# Board.net
KiCad netlist of a schematic drawn in Altium Designer
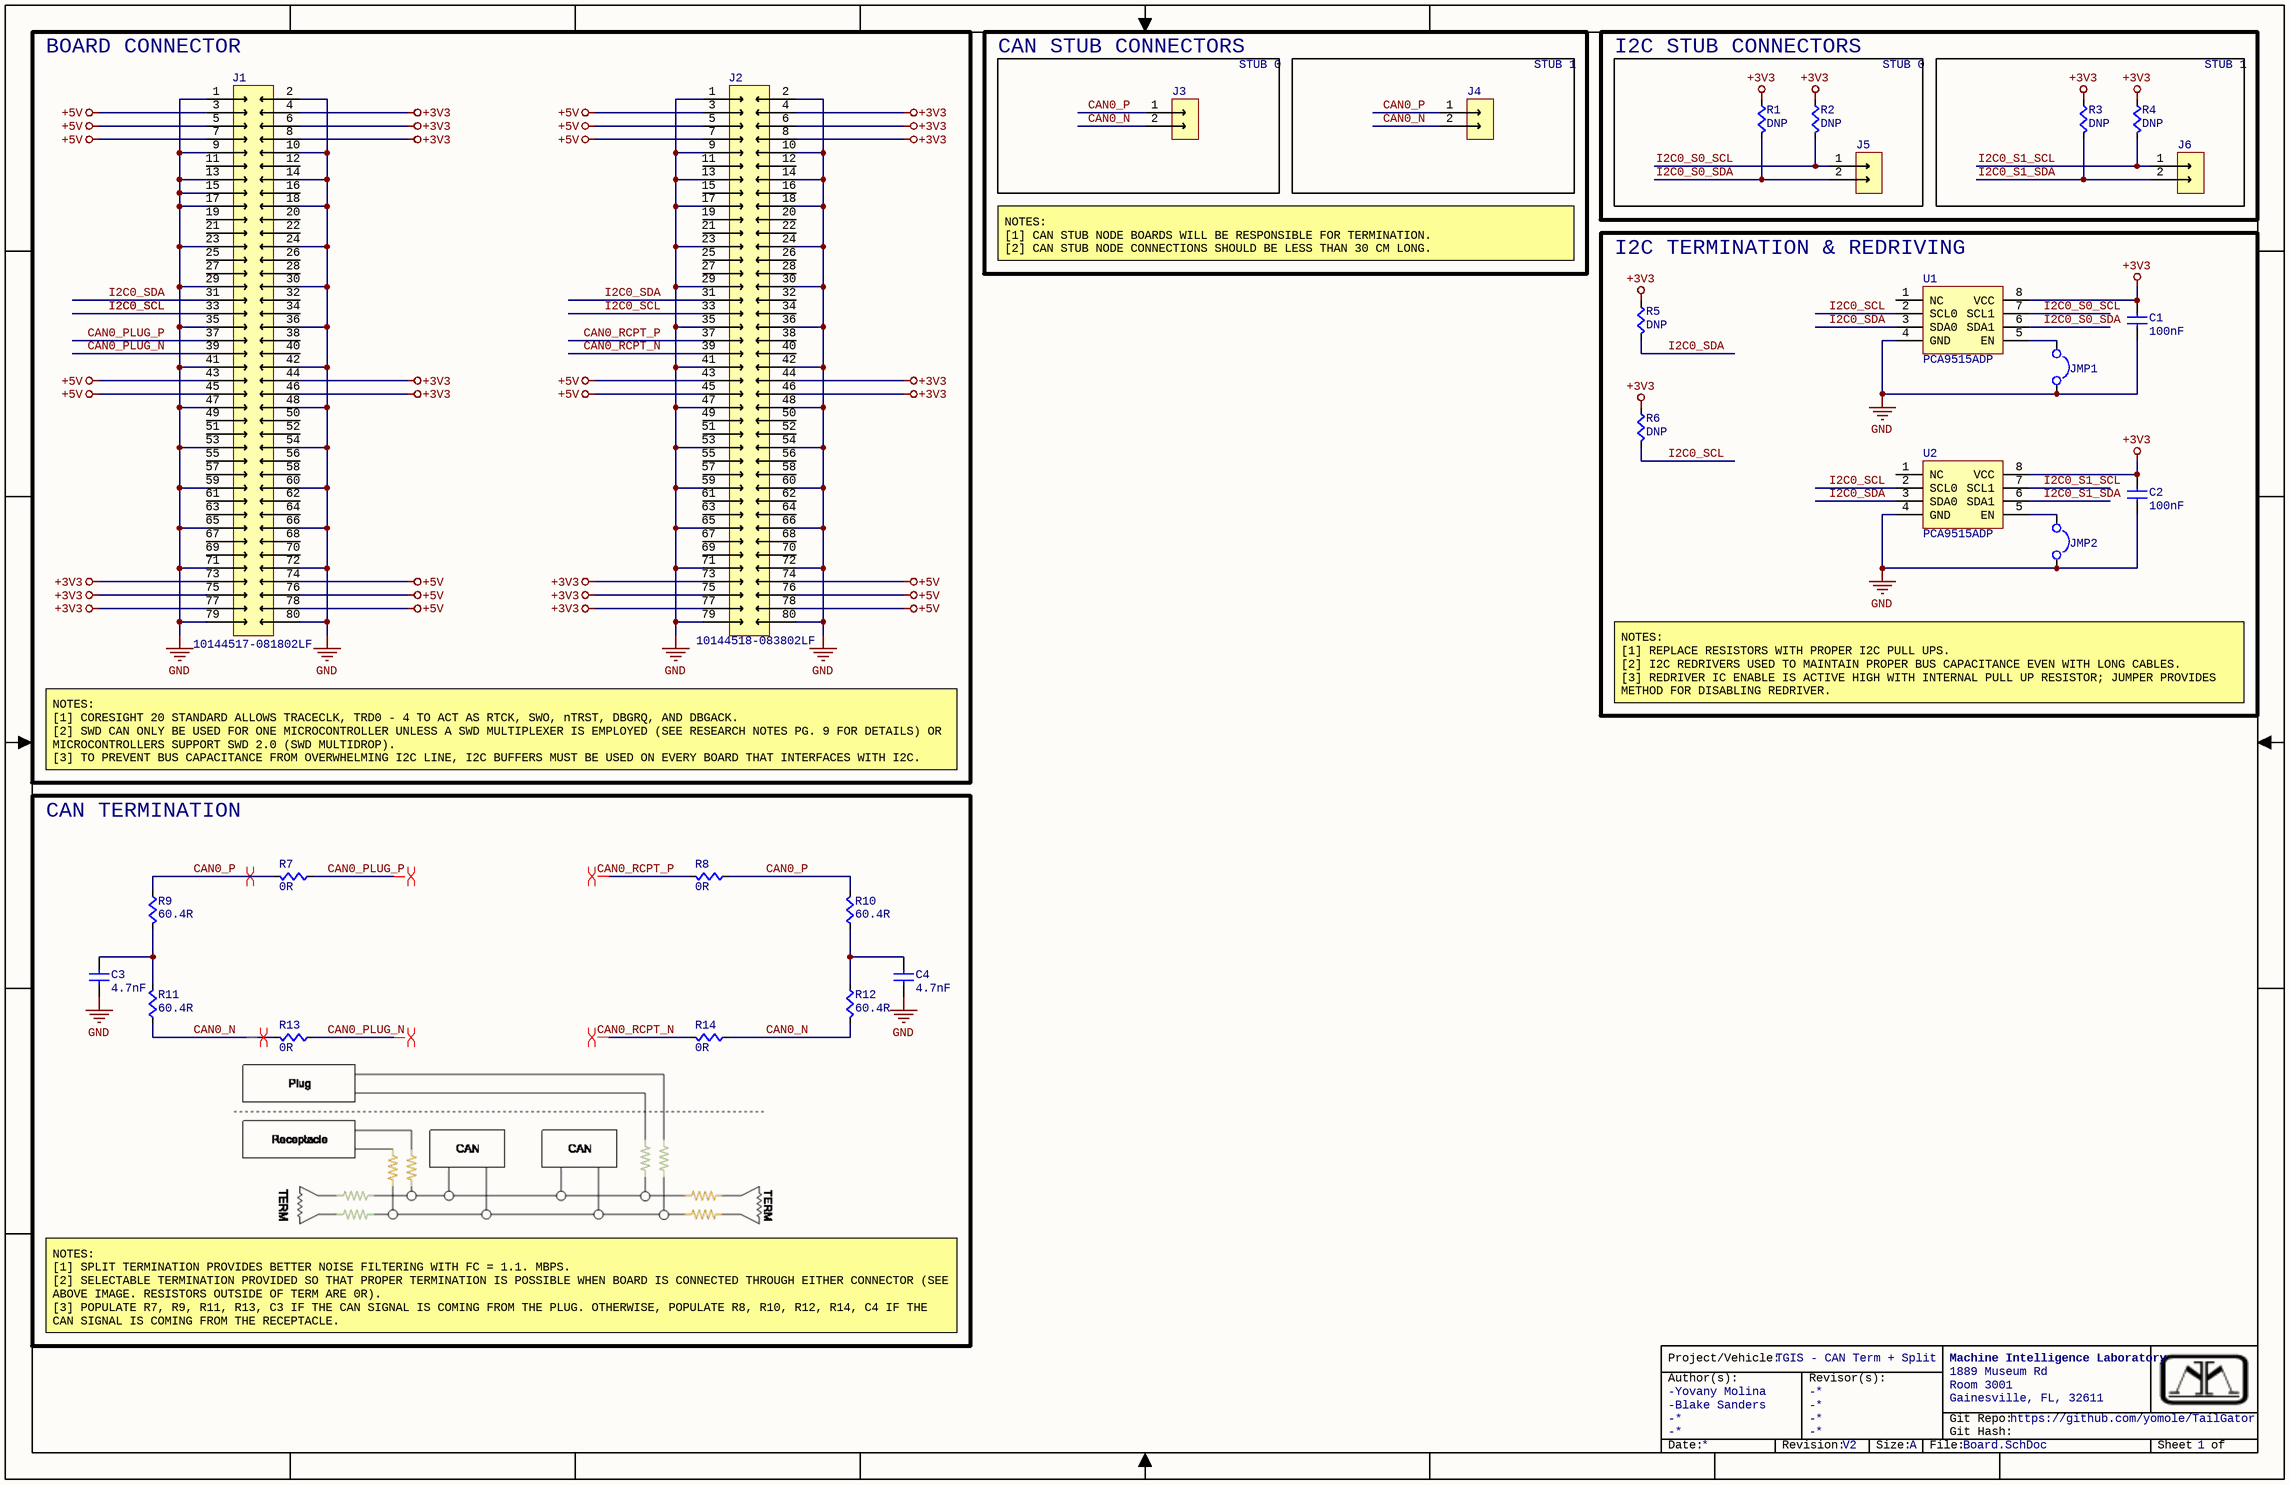
[diagram p0: Board.SchDoc]

(export (version "E")
  (design (tool "Eeschema 10.0.6"))
  (components
    (comp (ref "C1")
      (value "100nF")
      (footprint "CAPC0603")
      (description "Ceramic Capacitor, Multilayer, Cera")
      (fields (field (name "PART NUMBER") "CC0603KRX7R7BB104") (field (name "MANUFACTURER") "Yageo"))
      (libsource (lib "Parts") (part "NP_Capacitor"))
    )
    (comp (ref "C2")
      (value "100nF")
      (footprint "CAPC0603")
      (description "Ceramic Capacitor, Multilayer, Cera")
      (fields (field (name "PART NUMBER") "CC0603KRX7R7BB104") (field (name "MANUFACTURER") "Yageo"))
      (libsource (lib "Parts") (part "NP_Capacitor"))
    )
    (comp (ref "C3")
      (value "4.7nF")
      (footprint "CAPC0603")
      (description "Ceramic Capacitor, Multilayer, Cera")
      (fields (field (name "PART NUMBER") "CC0603JPX7R9BB472") (field (name "MANUFACTURER") "Yageo"))
      (libsource (lib "Parts") (part "NP_Capacitor"))
    )
    (comp (ref "C4")
      (value "4.7nF")
      (footprint "CAPC0603")
      (description "Ceramic Capacitor, Multilayer, Cera")
      (fields (field (name "PART NUMBER") "CC0603JPX7R9BB472") (field (name "MANUFACTURER") "Yageo"))
      (libsource (lib "Parts") (part "NP_Capacitor"))
    )
    (comp (ref "J1")
      (value "10144517-081802LF")
      (footprint "AMPHENOL_10144517-081802LF")
      (description "CONN RCPT 1 80POS SMD GOLD")
      (libsource (lib "TGIS") (part "10144517-081802LF"))
    )
    (comp (ref "J2")
      (value "10144518-083802LF")
      (footprint "AMPHENOL_10144518-083802LF")
      (description "CONN PLUG 3 80POS SMD GOLD")
      (libsource (lib "TGIS") (part "10144518-083802LF"))
    )
    (comp (ref "J3")
      (value "0353630260")
      (footprint "MOLEX-HDR-1X2-SHERLOCK-HORZ")
      (fields (field (name "MANUFACTURER") "Molex Inc"))
      (libsource (lib "Connectors") (part "SHERLOCK-1x2-RA"))
    )
    (comp (ref "J4")
      (value "0353630260")
      (footprint "MOLEX-HDR-1X2-SHERLOCK-HORZ")
      (fields (field (name "MANUFACTURER") "Molex Inc"))
      (libsource (lib "Connectors") (part "SHERLOCK-1x2-RA"))
    )
    (comp (ref "J5")
      (value "0353630260")
      (footprint "MOLEX-HDR-1X2-SHERLOCK-HORZ")
      (fields (field (name "MANUFACTURER") "Molex Inc"))
      (libsource (lib "Connectors") (part "SHERLOCK-1x2-RA"))
    )
    (comp (ref "J6")
      (value "0353630260")
      (footprint "MOLEX-HDR-1X2-SHERLOCK-HORZ")
      (fields (field (name "MANUFACTURER") "Molex Inc"))
      (libsource (lib "Connectors") (part "SHERLOCK-1x2-RA"))
    )
    (comp (ref "JMP1")
      (value "2 Pin Header")
      (footprint "2PinJumper")
      (description "2 Position Jumper")
      (libsource (lib "Misc") (part "Jumper_2Pin"))
    )
    (comp (ref "JMP2")
      (value "2 Pin Header")
      (footprint "2PinJumper")
      (description "2 Position Jumper")
      (libsource (lib "Misc") (part "Jumper_2Pin"))
    )
    (comp (ref "R1")
      (value "DNP")
      (footprint "RES0603")
      (description "(DO NOT PLACE) Resistor")
      (libsource (lib "DNP") (part "Resistor_DNP"))
    )
    (comp (ref "R2")
      (value "DNP")
      (footprint "RES0603")
      (description "(DO NOT PLACE) Resistor")
      (libsource (lib "DNP") (part "Resistor_DNP"))
    )
    (comp (ref "R3")
      (value "DNP")
      (footprint "RES0603")
      (description "(DO NOT PLACE) Resistor")
      (libsource (lib "DNP") (part "Resistor_DNP"))
    )
    (comp (ref "R4")
      (value "DNP")
      (footprint "RES0603")
      (description "(DO NOT PLACE) Resistor")
      (libsource (lib "DNP") (part "Resistor_DNP"))
    )
    (comp (ref "R5")
      (value "DNP")
      (footprint "RES0603")
      (description "(DO NOT PLACE) Resistor")
      (libsource (lib "DNP") (part "Resistor_DNP"))
    )
    (comp (ref "R6")
      (value "DNP")
      (footprint "RES0603")
      (description "(DO NOT PLACE) Resistor")
      (libsource (lib "DNP") (part "Resistor_DNP"))
    )
    (comp (ref "R7")
      (value "0R")
      (footprint "RES0603")
      (description "Fixed Resistor, Metal Glaze/thick F")
      (fields (field (name "PART NUMBER") "RC0603FR-070RL") (field (name "POWER") "100mW"))
      (libsource (lib "Parts") (part "Resistor"))
    )
    (comp (ref "R8")
      (value "0R")
      (footprint "RES0603")
      (description "Fixed Resistor, Metal Glaze/thick F")
      (fields (field (name "PART NUMBER") "RC0603FR-070RL") (field (name "POWER") "100mW"))
      (libsource (lib "Parts") (part "Resistor"))
    )
    (comp (ref "R9")
      (value "60.4R")
      (footprint "RES0603")
      (description "Fixed Resistor, Metal Glaze/thick F")
      (fields (field (name "PART NUMBER") "RC0603FR-0760R4L") (field (name "POWER") "100mW"))
      (libsource (lib "Parts") (part "Resistor"))
    )
    (comp (ref "R10")
      (value "60.4R")
      (footprint "RES0603")
      (description "Fixed Resistor, Metal Glaze/thick F")
      (fields (field (name "PART NUMBER") "RC0603FR-0760R4L") (field (name "POWER") "100mW"))
      (libsource (lib "Parts") (part "Resistor"))
    )
    (comp (ref "R11")
      (value "60.4R")
      (footprint "RES0603")
      (description "Fixed Resistor, Metal Glaze/thick F")
      (fields (field (name "PART NUMBER") "RC0603FR-0760R4L") (field (name "POWER") "100mW"))
      (libsource (lib "Parts") (part "Resistor"))
    )
    (comp (ref "R12")
      (value "60.4R")
      (footprint "RES0603")
      (description "Fixed Resistor, Metal Glaze/thick F")
      (fields (field (name "PART NUMBER") "RC0603FR-0760R4L") (field (name "POWER") "100mW"))
      (libsource (lib "Parts") (part "Resistor"))
    )
    (comp (ref "R13")
      (value "0R")
      (footprint "RES0603")
      (description "Fixed Resistor, Metal Glaze/thick F")
      (fields (field (name "PART NUMBER") "RC0603FR-070RL") (field (name "POWER") "100mW"))
      (libsource (lib "Parts") (part "Resistor"))
    )
    (comp (ref "R14")
      (value "0R")
      (footprint "RES0603")
      (description "Fixed Resistor, Metal Glaze/thick F")
      (fields (field (name "PART NUMBER") "RC0603FR-070RL") (field (name "POWER") "100mW"))
      (libsource (lib "Parts") (part "Resistor"))
    )
    (comp (ref "U1")
      (value "PCA9515ADP")
      (footprint "SOP65P490X110-8N")
      (description "IC REDRIVER I2C 2CH 8TSSOP")
      (libsource (lib "TGIS") (part "PCA9515ADP"))
    )
    (comp (ref "U2")
      (value "PCA9515ADP")
      (footprint "SOP65P490X110-8N")
      (description "IC REDRIVER I2C 2CH 8TSSOP")
      (libsource (lib "TGIS") (part "PCA9515ADP"))
    )
  )
  (nets
    (net (code "1") (name "+3V3") (class "Default")
      (node (ref "C1") (pin "2") (pinfunction "B_2") (pintype "passive"))
      (node (ref "C2") (pin "2") (pinfunction "B_2") (pintype "passive"))
      (node (ref "J1") (pin "4") (pinfunction "4_4") (pintype "passive"))
      (node (ref "J1") (pin "44") (pinfunction "44_44") (pintype "passive"))
      (node (ref "J1") (pin "46") (pinfunction "46_46") (pintype "passive"))
      (node (ref "J1") (pin "6") (pinfunction "6_6") (pintype "passive"))
      (node (ref "J1") (pin "73") (pinfunction "73_73") (pintype "passive"))
      (node (ref "J1") (pin "75") (pinfunction "75_75") (pintype "passive"))
      (node (ref "J1") (pin "77") (pinfunction "77_77") (pintype "passive"))
      (node (ref "J1") (pin "8") (pinfunction "8_8") (pintype "passive"))
      (node (ref "J2") (pin "4") (pinfunction "4_4") (pintype "passive"))
      (node (ref "J2") (pin "44") (pinfunction "44_44") (pintype "passive"))
      (node (ref "J2") (pin "46") (pinfunction "46_46") (pintype "passive"))
      (node (ref "J2") (pin "6") (pinfunction "6_6") (pintype "passive"))
      (node (ref "J2") (pin "73") (pinfunction "73_73") (pintype "passive"))
      (node (ref "J2") (pin "75") (pinfunction "75_75") (pintype "passive"))
      (node (ref "J2") (pin "77") (pinfunction "77_77") (pintype "passive"))
      (node (ref "J2") (pin "8") (pinfunction "8_8") (pintype "passive"))
      (node (ref "R1") (pin "2") (pinfunction "B_2") (pintype "passive"))
      (node (ref "R2") (pin "2") (pinfunction "B_2") (pintype "passive"))
      (node (ref "R3") (pin "2") (pinfunction "B_2") (pintype "passive"))
      (node (ref "R4") (pin "2") (pinfunction "B_2") (pintype "passive"))
      (node (ref "R5") (pin "2") (pinfunction "B_2") (pintype "passive"))
      (node (ref "R6") (pin "2") (pinfunction "B_2") (pintype "passive"))
      (node (ref "U1") (pin "8") (pinfunction "VCC_8") (pintype "passive"))
      (node (ref "U2") (pin "8") (pinfunction "VCC_8") (pintype "passive"))
    )
    (net (code "2") (name "+5V") (class "Default")
      (node (ref "J1") (pin "3") (pinfunction "3_3") (pintype "passive"))
      (node (ref "J1") (pin "43") (pinfunction "43_43") (pintype "passive"))
      (node (ref "J1") (pin "45") (pinfunction "45_45") (pintype "passive"))
      (node (ref "J1") (pin "5") (pinfunction "5_5") (pintype "passive"))
      (node (ref "J1") (pin "7") (pinfunction "7_7") (pintype "passive"))
      (node (ref "J1") (pin "74") (pinfunction "74_74") (pintype "passive"))
      (node (ref "J1") (pin "76") (pinfunction "76_76") (pintype "passive"))
      (node (ref "J1") (pin "78") (pinfunction "78_78") (pintype "passive"))
      (node (ref "J2") (pin "3") (pinfunction "3_3") (pintype "passive"))
      (node (ref "J2") (pin "43") (pinfunction "43_43") (pintype "passive"))
      (node (ref "J2") (pin "45") (pinfunction "45_45") (pintype "passive"))
      (node (ref "J2") (pin "5") (pinfunction "5_5") (pintype "passive"))
      (node (ref "J2") (pin "7") (pinfunction "7_7") (pintype "passive"))
      (node (ref "J2") (pin "74") (pinfunction "74_74") (pintype "passive"))
      (node (ref "J2") (pin "76") (pinfunction "76_76") (pintype "passive"))
      (node (ref "J2") (pin "78") (pinfunction "78_78") (pintype "passive"))
    )
    (net (code "3") (name "/CAN0_N") (class "Default")
      (node (ref "J3") (pin "2") (pinfunction "2_2") (pintype "passive"))
      (node (ref "J4") (pin "2") (pinfunction "2_2") (pintype "passive"))
      (node (ref "R11") (pin "2") (pinfunction "B_2") (pintype "passive"))
      (node (ref "R12") (pin "2") (pinfunction "B_2") (pintype "passive"))
      (node (ref "R13") (pin "1") (pinfunction "A_1") (pintype "passive"))
      (node (ref "R14") (pin "2") (pinfunction "B_2") (pintype "passive"))
    )
    (net (code "4") (name "/CAN0_P") (class "Default")
      (node (ref "J3") (pin "1") (pinfunction "1_1") (pintype "passive"))
      (node (ref "J4") (pin "1") (pinfunction "1_1") (pintype "passive"))
      (node (ref "R10") (pin "2") (pinfunction "B_2") (pintype "passive"))
      (node (ref "R7") (pin "1") (pinfunction "A_1") (pintype "passive"))
      (node (ref "R8") (pin "2") (pinfunction "B_2") (pintype "passive"))
      (node (ref "R9") (pin "2") (pinfunction "B_2") (pintype "passive"))
    )
    (net (code "5") (name "/CAN0_PLUG_N") (class "Default")
      (node (ref "J1") (pin "39") (pinfunction "39_39") (pintype "passive"))
      (node (ref "R13") (pin "2") (pinfunction "B_2") (pintype "passive"))
    )
    (net (code "6") (name "/CAN0_PLUG_P") (class "Default")
      (node (ref "J1") (pin "37") (pinfunction "37_37") (pintype "passive"))
      (node (ref "R7") (pin "2") (pinfunction "B_2") (pintype "passive"))
    )
    (net (code "7") (name "/CAN0_RCPT_N") (class "Default")
      (node (ref "J2") (pin "39") (pinfunction "39_39") (pintype "passive"))
      (node (ref "R14") (pin "1") (pinfunction "A_1") (pintype "passive"))
    )
    (net (code "8") (name "/CAN0_RCPT_P") (class "Default")
      (node (ref "J2") (pin "37") (pinfunction "37_37") (pintype "passive"))
      (node (ref "R8") (pin "1") (pinfunction "A_1") (pintype "passive"))
    )
    (net (code "9") (name "/I2C0_S0_SCL") (class "Default")
      (node (ref "J5") (pin "1") (pinfunction "1_1") (pintype "passive"))
      (node (ref "R2") (pin "1") (pinfunction "A_1") (pintype "passive"))
      (node (ref "U1") (pin "7") (pinfunction "SCL1_7") (pintype "passive"))
    )
    (net (code "10") (name "/I2C0_S0_SDA") (class "Default")
      (node (ref "J5") (pin "2") (pinfunction "2_2") (pintype "passive"))
      (node (ref "R1") (pin "1") (pinfunction "A_1") (pintype "passive"))
      (node (ref "U1") (pin "6") (pinfunction "SDA1_6") (pintype "passive"))
    )
    (net (code "11") (name "/I2C0_S1_SCL") (class "Default")
      (node (ref "J6") (pin "1") (pinfunction "1_1") (pintype "passive"))
      (node (ref "R4") (pin "1") (pinfunction "A_1") (pintype "passive"))
      (node (ref "U2") (pin "7") (pinfunction "SCL1_7") (pintype "passive"))
    )
    (net (code "12") (name "/I2C0_S1_SDA") (class "Default")
      (node (ref "J6") (pin "2") (pinfunction "2_2") (pintype "passive"))
      (node (ref "R3") (pin "1") (pinfunction "A_1") (pintype "passive"))
      (node (ref "U2") (pin "6") (pinfunction "SDA1_6") (pintype "passive"))
    )
    (net (code "13") (name "/I2C0_SCL") (class "Default")
      (node (ref "J1") (pin "33") (pinfunction "33_33") (pintype "passive"))
      (node (ref "J2") (pin "33") (pinfunction "33_33") (pintype "passive"))
      (node (ref "R6") (pin "1") (pinfunction "A_1") (pintype "passive"))
      (node (ref "U1") (pin "2") (pinfunction "SCL0_2") (pintype "passive"))
      (node (ref "U2") (pin "2") (pinfunction "SCL0_2") (pintype "passive"))
    )
    (net (code "14") (name "/I2C0_SDA") (class "Default")
      (node (ref "J1") (pin "31") (pinfunction "31_31") (pintype "passive"))
      (node (ref "J2") (pin "31") (pinfunction "31_31") (pintype "passive"))
      (node (ref "R5") (pin "1") (pinfunction "A_1") (pintype "passive"))
      (node (ref "U1") (pin "3") (pinfunction "SDA0_3") (pintype "passive"))
      (node (ref "U2") (pin "3") (pinfunction "SDA0_3") (pintype "passive"))
    )
    (net (code "15") (name "GND") (class "Default")
      (node (ref "C1") (pin "1") (pinfunction "A_1") (pintype "passive"))
      (node (ref "C2") (pin "1") (pinfunction "A_1") (pintype "passive"))
      (node (ref "C3") (pin "2") (pinfunction "B_2") (pintype "passive"))
      (node (ref "C4") (pin "2") (pinfunction "B_2") (pintype "passive"))
      (node (ref "J1") (pin "1") (pinfunction "1_1") (pintype "passive"))
      (node (ref "J1") (pin "10") (pinfunction "10_10") (pintype "passive"))
      (node (ref "J1") (pin "13") (pinfunction "13_13") (pintype "passive"))
      (node (ref "J1") (pin "14") (pinfunction "14_14") (pintype "passive"))
      (node (ref "J1") (pin "15") (pinfunction "15_15") (pintype "passive"))
      (node (ref "J1") (pin "17") (pinfunction "17_17") (pintype "passive"))
      (node (ref "J1") (pin "18") (pinfunction "18_18") (pintype "passive"))
      (node (ref "J1") (pin "2") (pinfunction "2_2") (pintype "passive"))
      (node (ref "J1") (pin "23") (pinfunction "23_23") (pintype "passive"))
      (node (ref "J1") (pin "24") (pinfunction "24_24") (pintype "passive"))
      (node (ref "J1") (pin "29") (pinfunction "29_29") (pintype "passive"))
      (node (ref "J1") (pin "30") (pinfunction "30_30") (pintype "passive"))
      (node (ref "J1") (pin "35") (pinfunction "35_35") (pintype "passive"))
      (node (ref "J1") (pin "36") (pinfunction "36_36") (pintype "passive"))
      (node (ref "J1") (pin "41") (pinfunction "41_41") (pintype "passive"))
      (node (ref "J1") (pin "42") (pinfunction "42_42") (pintype "passive"))
      (node (ref "J1") (pin "47") (pinfunction "47_47") (pintype "passive"))
      (node (ref "J1") (pin "48") (pinfunction "48_48") (pintype "passive"))
      (node (ref "J1") (pin "53") (pinfunction "53_53") (pintype "passive"))
      (node (ref "J1") (pin "54") (pinfunction "54_54") (pintype "passive"))
      (node (ref "J1") (pin "59") (pinfunction "59_59") (pintype "passive"))
      (node (ref "J1") (pin "60") (pinfunction "60_60") (pintype "passive"))
      (node (ref "J1") (pin "65") (pinfunction "65_65") (pintype "passive"))
      (node (ref "J1") (pin "66") (pinfunction "66_66") (pintype "passive"))
      (node (ref "J1") (pin "71") (pinfunction "71_71") (pintype "passive"))
      (node (ref "J1") (pin "72") (pinfunction "72_72") (pintype "passive"))
      (node (ref "J1") (pin "79") (pinfunction "79_79") (pintype "passive"))
      (node (ref "J1") (pin "80") (pinfunction "80_80") (pintype "passive"))
      (node (ref "J1") (pin "9") (pinfunction "9_9") (pintype "passive"))
      (node (ref "J2") (pin "1") (pinfunction "1_1") (pintype "passive"))
      (node (ref "J2") (pin "10") (pinfunction "10_10") (pintype "passive"))
      (node (ref "J2") (pin "13") (pinfunction "13_13") (pintype "passive"))
      (node (ref "J2") (pin "14") (pinfunction "14_14") (pintype "passive"))
      (node (ref "J2") (pin "17") (pinfunction "17_17") (pintype "passive"))
      (node (ref "J2") (pin "18") (pinfunction "18_18") (pintype "passive"))
      (node (ref "J2") (pin "2") (pinfunction "2_2") (pintype "passive"))
      (node (ref "J2") (pin "23") (pinfunction "23_23") (pintype "passive"))
      (node (ref "J2") (pin "24") (pinfunction "24_24") (pintype "passive"))
      (node (ref "J2") (pin "29") (pinfunction "29_29") (pintype "passive"))
      (node (ref "J2") (pin "30") (pinfunction "30_30") (pintype "passive"))
      (node (ref "J2") (pin "35") (pinfunction "35_35") (pintype "passive"))
      (node (ref "J2") (pin "36") (pinfunction "36_36") (pintype "passive"))
      (node (ref "J2") (pin "41") (pinfunction "41_41") (pintype "passive"))
      (node (ref "J2") (pin "42") (pinfunction "42_42") (pintype "passive"))
      (node (ref "J2") (pin "47") (pinfunction "47_47") (pintype "passive"))
      (node (ref "J2") (pin "48") (pinfunction "48_48") (pintype "passive"))
      (node (ref "J2") (pin "53") (pinfunction "53_53") (pintype "passive"))
      (node (ref "J2") (pin "54") (pinfunction "54_54") (pintype "passive"))
      (node (ref "J2") (pin "59") (pinfunction "59_59") (pintype "passive"))
      (node (ref "J2") (pin "60") (pinfunction "60_60") (pintype "passive"))
      (node (ref "J2") (pin "65") (pinfunction "65_65") (pintype "passive"))
      (node (ref "J2") (pin "66") (pinfunction "66_66") (pintype "passive"))
      (node (ref "J2") (pin "71") (pinfunction "71_71") (pintype "passive"))
      (node (ref "J2") (pin "72") (pinfunction "72_72") (pintype "passive"))
      (node (ref "J2") (pin "79") (pinfunction "79_79") (pintype "passive"))
      (node (ref "J2") (pin "80") (pinfunction "80_80") (pintype "passive"))
      (node (ref "J2") (pin "9") (pinfunction "9_9") (pintype "passive"))
      (node (ref "JMP1") (pin "2") (pinfunction "2_2") (pintype "passive"))
      (node (ref "JMP2") (pin "2") (pinfunction "2_2") (pintype "passive"))
      (node (ref "U1") (pin "4") (pinfunction "GND_4") (pintype "passive"))
      (node (ref "U2") (pin "4") (pinfunction "GND_4") (pintype "passive"))
    )
    (net (code "16") (name "Net-(C3-A)") (class "Default")
      (node (ref "C3") (pin "1") (pinfunction "A_1") (pintype "passive"))
      (node (ref "R11") (pin "1") (pinfunction "A_1") (pintype "passive"))
      (node (ref "R9") (pin "1") (pinfunction "A_1") (pintype "passive"))
    )
    (net (code "17") (name "Net-(C4-A)") (class "Default")
      (node (ref "C4") (pin "1") (pinfunction "A_1") (pintype "passive"))
      (node (ref "R10") (pin "1") (pinfunction "A_1") (pintype "passive"))
      (node (ref "R12") (pin "1") (pinfunction "A_1") (pintype "passive"))
    )
    (net (code "18") (name "Net-(U1-EN)") (class "Default")
      (node (ref "JMP1") (pin "1") (pinfunction "1_1") (pintype "passive"))
      (node (ref "U1") (pin "5") (pinfunction "EN_5") (pintype "passive"))
    )
    (net (code "19") (name "Net-(U2-EN)") (class "Default")
      (node (ref "JMP2") (pin "1") (pinfunction "1_1") (pintype "passive"))
      (node (ref "U2") (pin "5") (pinfunction "EN_5") (pintype "passive"))
    )
    (net (code "20") (name "unconnected-(J1-Pad11)") (class "Default")
      (node (ref "J1") (pin "11") (pinfunction "11_11") (pintype "passive"))
    )
    (net (code "21") (name "unconnected-(J1-Pad12)") (class "Default")
      (node (ref "J1") (pin "12") (pinfunction "12_12") (pintype "passive"))
    )
    (net (code "22") (name "unconnected-(J1-Pad16)") (class "Default")
      (node (ref "J1") (pin "16") (pinfunction "16_16") (pintype "passive"))
    )
    (net (code "23") (name "unconnected-(J1-Pad19)") (class "Default")
      (node (ref "J1") (pin "19") (pinfunction "19_19") (pintype "passive"))
    )
    (net (code "24") (name "unconnected-(J1-Pad20)") (class "Default")
      (node (ref "J1") (pin "20") (pinfunction "20_20") (pintype "passive"))
    )
    (net (code "25") (name "unconnected-(J1-Pad21)") (class "Default")
      (node (ref "J1") (pin "21") (pinfunction "21_21") (pintype "passive"))
    )
    (net (code "26") (name "unconnected-(J1-Pad22)") (class "Default")
      (node (ref "J1") (pin "22") (pinfunction "22_22") (pintype "passive"))
    )
    (net (code "27") (name "unconnected-(J1-Pad25)") (class "Default")
      (node (ref "J1") (pin "25") (pinfunction "25_25") (pintype "passive"))
    )
    (net (code "28") (name "unconnected-(J1-Pad26)") (class "Default")
      (node (ref "J1") (pin "26") (pinfunction "26_26") (pintype "passive"))
    )
    (net (code "29") (name "unconnected-(J1-Pad27)") (class "Default")
      (node (ref "J1") (pin "27") (pinfunction "27_27") (pintype "passive"))
    )
    (net (code "30") (name "unconnected-(J1-Pad28)") (class "Default")
      (node (ref "J1") (pin "28") (pinfunction "28_28") (pintype "passive"))
    )
    (net (code "31") (name "unconnected-(J1-Pad32)") (class "Default")
      (node (ref "J1") (pin "32") (pinfunction "32_32") (pintype "passive"))
    )
    (net (code "32") (name "unconnected-(J1-Pad34)") (class "Default")
      (node (ref "J1") (pin "34") (pinfunction "34_34") (pintype "passive"))
    )
    (net (code "33") (name "unconnected-(J1-Pad38)") (class "Default")
      (node (ref "J1") (pin "38") (pinfunction "38_38") (pintype "passive"))
    )
    (net (code "34") (name "unconnected-(J1-Pad40)") (class "Default")
      (node (ref "J1") (pin "40") (pinfunction "40_40") (pintype "passive"))
    )
    (net (code "35") (name "unconnected-(J1-Pad49)") (class "Default")
      (node (ref "J1") (pin "49") (pinfunction "49_49") (pintype "passive"))
    )
    (net (code "36") (name "unconnected-(J1-Pad50)") (class "Default")
      (node (ref "J1") (pin "50") (pinfunction "50_50") (pintype "passive"))
    )
    (net (code "37") (name "unconnected-(J1-Pad51)") (class "Default")
      (node (ref "J1") (pin "51") (pinfunction "51_51") (pintype "passive"))
    )
    (net (code "38") (name "unconnected-(J1-Pad52)") (class "Default")
      (node (ref "J1") (pin "52") (pinfunction "52_52") (pintype "passive"))
    )
    (net (code "39") (name "unconnected-(J1-Pad55)") (class "Default")
      (node (ref "J1") (pin "55") (pinfunction "55_55") (pintype "passive"))
    )
    (net (code "40") (name "unconnected-(J1-Pad56)") (class "Default")
      (node (ref "J1") (pin "56") (pinfunction "56_56") (pintype "passive"))
    )
    (net (code "41") (name "unconnected-(J1-Pad57)") (class "Default")
      (node (ref "J1") (pin "57") (pinfunction "57_57") (pintype "passive"))
    )
    (net (code "42") (name "unconnected-(J1-Pad58)") (class "Default")
      (node (ref "J1") (pin "58") (pinfunction "58_58") (pintype "passive"))
    )
    (net (code "43") (name "unconnected-(J1-Pad61)") (class "Default")
      (node (ref "J1") (pin "61") (pinfunction "61_61") (pintype "passive"))
    )
    (net (code "44") (name "unconnected-(J1-Pad62)") (class "Default")
      (node (ref "J1") (pin "62") (pinfunction "62_62") (pintype "passive"))
    )
    (net (code "45") (name "unconnected-(J1-Pad63)") (class "Default")
      (node (ref "J1") (pin "63") (pinfunction "63_63") (pintype "passive"))
    )
    (net (code "46") (name "unconnected-(J1-Pad64)") (class "Default")
      (node (ref "J1") (pin "64") (pinfunction "64_64") (pintype "passive"))
    )
    (net (code "47") (name "unconnected-(J1-Pad67)") (class "Default")
      (node (ref "J1") (pin "67") (pinfunction "67_67") (pintype "passive"))
    )
    (net (code "48") (name "unconnected-(J1-Pad68)") (class "Default")
      (node (ref "J1") (pin "68") (pinfunction "68_68") (pintype "passive"))
    )
    (net (code "49") (name "unconnected-(J1-Pad69)") (class "Default")
      (node (ref "J1") (pin "69") (pinfunction "69_69") (pintype "passive"))
    )
    (net (code "50") (name "unconnected-(J1-Pad70)") (class "Default")
      (node (ref "J1") (pin "70") (pinfunction "70_70") (pintype "passive"))
    )
    (net (code "51") (name "unconnected-(J2-Pad11)") (class "Default")
      (node (ref "J2") (pin "11") (pinfunction "11_11") (pintype "passive"))
    )
    (net (code "52") (name "unconnected-(J2-Pad12)") (class "Default")
      (node (ref "J2") (pin "12") (pinfunction "12_12") (pintype "passive"))
    )
    (net (code "53") (name "unconnected-(J2-Pad15)") (class "Default")
      (node (ref "J2") (pin "15") (pinfunction "15_15") (pintype "passive"))
    )
    (net (code "54") (name "unconnected-(J2-Pad16)") (class "Default")
      (node (ref "J2") (pin "16") (pinfunction "16_16") (pintype "passive"))
    )
    (net (code "55") (name "unconnected-(J2-Pad19)") (class "Default")
      (node (ref "J2") (pin "19") (pinfunction "19_19") (pintype "passive"))
    )
    (net (code "56") (name "unconnected-(J2-Pad20)") (class "Default")
      (node (ref "J2") (pin "20") (pinfunction "20_20") (pintype "passive"))
    )
    (net (code "57") (name "unconnected-(J2-Pad21)") (class "Default")
      (node (ref "J2") (pin "21") (pinfunction "21_21") (pintype "passive"))
    )
    (net (code "58") (name "unconnected-(J2-Pad22)") (class "Default")
      (node (ref "J2") (pin "22") (pinfunction "22_22") (pintype "passive"))
    )
    (net (code "59") (name "unconnected-(J2-Pad25)") (class "Default")
      (node (ref "J2") (pin "25") (pinfunction "25_25") (pintype "passive"))
    )
    (net (code "60") (name "unconnected-(J2-Pad26)") (class "Default")
      (node (ref "J2") (pin "26") (pinfunction "26_26") (pintype "passive"))
    )
    (net (code "61") (name "unconnected-(J2-Pad27)") (class "Default")
      (node (ref "J2") (pin "27") (pinfunction "27_27") (pintype "passive"))
    )
    (net (code "62") (name "unconnected-(J2-Pad28)") (class "Default")
      (node (ref "J2") (pin "28") (pinfunction "28_28") (pintype "passive"))
    )
    (net (code "63") (name "unconnected-(J2-Pad32)") (class "Default")
      (node (ref "J2") (pin "32") (pinfunction "32_32") (pintype "passive"))
    )
    (net (code "64") (name "unconnected-(J2-Pad34)") (class "Default")
      (node (ref "J2") (pin "34") (pinfunction "34_34") (pintype "passive"))
    )
    (net (code "65") (name "unconnected-(J2-Pad38)") (class "Default")
      (node (ref "J2") (pin "38") (pinfunction "38_38") (pintype "passive"))
    )
    (net (code "66") (name "unconnected-(J2-Pad40)") (class "Default")
      (node (ref "J2") (pin "40") (pinfunction "40_40") (pintype "passive"))
    )
    (net (code "67") (name "unconnected-(J2-Pad49)") (class "Default")
      (node (ref "J2") (pin "49") (pinfunction "49_49") (pintype "passive"))
    )
    (net (code "68") (name "unconnected-(J2-Pad50)") (class "Default")
      (node (ref "J2") (pin "50") (pinfunction "50_50") (pintype "passive"))
    )
    (net (code "69") (name "unconnected-(J2-Pad51)") (class "Default")
      (node (ref "J2") (pin "51") (pinfunction "51_51") (pintype "passive"))
    )
    (net (code "70") (name "unconnected-(J2-Pad52)") (class "Default")
      (node (ref "J2") (pin "52") (pinfunction "52_52") (pintype "passive"))
    )
    (net (code "71") (name "unconnected-(J2-Pad55)") (class "Default")
      (node (ref "J2") (pin "55") (pinfunction "55_55") (pintype "passive"))
    )
    (net (code "72") (name "unconnected-(J2-Pad56)") (class "Default")
      (node (ref "J2") (pin "56") (pinfunction "56_56") (pintype "passive"))
    )
    (net (code "73") (name "unconnected-(J2-Pad57)") (class "Default")
      (node (ref "J2") (pin "57") (pinfunction "57_57") (pintype "passive"))
    )
    (net (code "74") (name "unconnected-(J2-Pad58)") (class "Default")
      (node (ref "J2") (pin "58") (pinfunction "58_58") (pintype "passive"))
    )
    (net (code "75") (name "unconnected-(J2-Pad61)") (class "Default")
      (node (ref "J2") (pin "61") (pinfunction "61_61") (pintype "passive"))
    )
    (net (code "76") (name "unconnected-(J2-Pad62)") (class "Default")
      (node (ref "J2") (pin "62") (pinfunction "62_62") (pintype "passive"))
    )
    (net (code "77") (name "unconnected-(J2-Pad63)") (class "Default")
      (node (ref "J2") (pin "63") (pinfunction "63_63") (pintype "passive"))
    )
    (net (code "78") (name "unconnected-(J2-Pad64)") (class "Default")
      (node (ref "J2") (pin "64") (pinfunction "64_64") (pintype "passive"))
    )
    (net (code "79") (name "unconnected-(J2-Pad67)") (class "Default")
      (node (ref "J2") (pin "67") (pinfunction "67_67") (pintype "passive"))
    )
    (net (code "80") (name "unconnected-(J2-Pad68)") (class "Default")
      (node (ref "J2") (pin "68") (pinfunction "68_68") (pintype "passive"))
    )
    (net (code "81") (name "unconnected-(J2-Pad69)") (class "Default")
      (node (ref "J2") (pin "69") (pinfunction "69_69") (pintype "passive"))
    )
    (net (code "82") (name "unconnected-(J2-Pad70)") (class "Default")
      (node (ref "J2") (pin "70") (pinfunction "70_70") (pintype "passive"))
    )
    (net (code "83") (name "unconnected-(U1-NC-Pad1)") (class "Default")
      (node (ref "U1") (pin "1") (pinfunction "NC_1") (pintype "passive"))
    )
    (net (code "84") (name "unconnected-(U2-NC-Pad1)") (class "Default")
      (node (ref "U2") (pin "1") (pinfunction "NC_1") (pintype "passive"))
    )
  )
)
